# Servos.net
KiCad netlist of a schematic drawn in Altium Designer
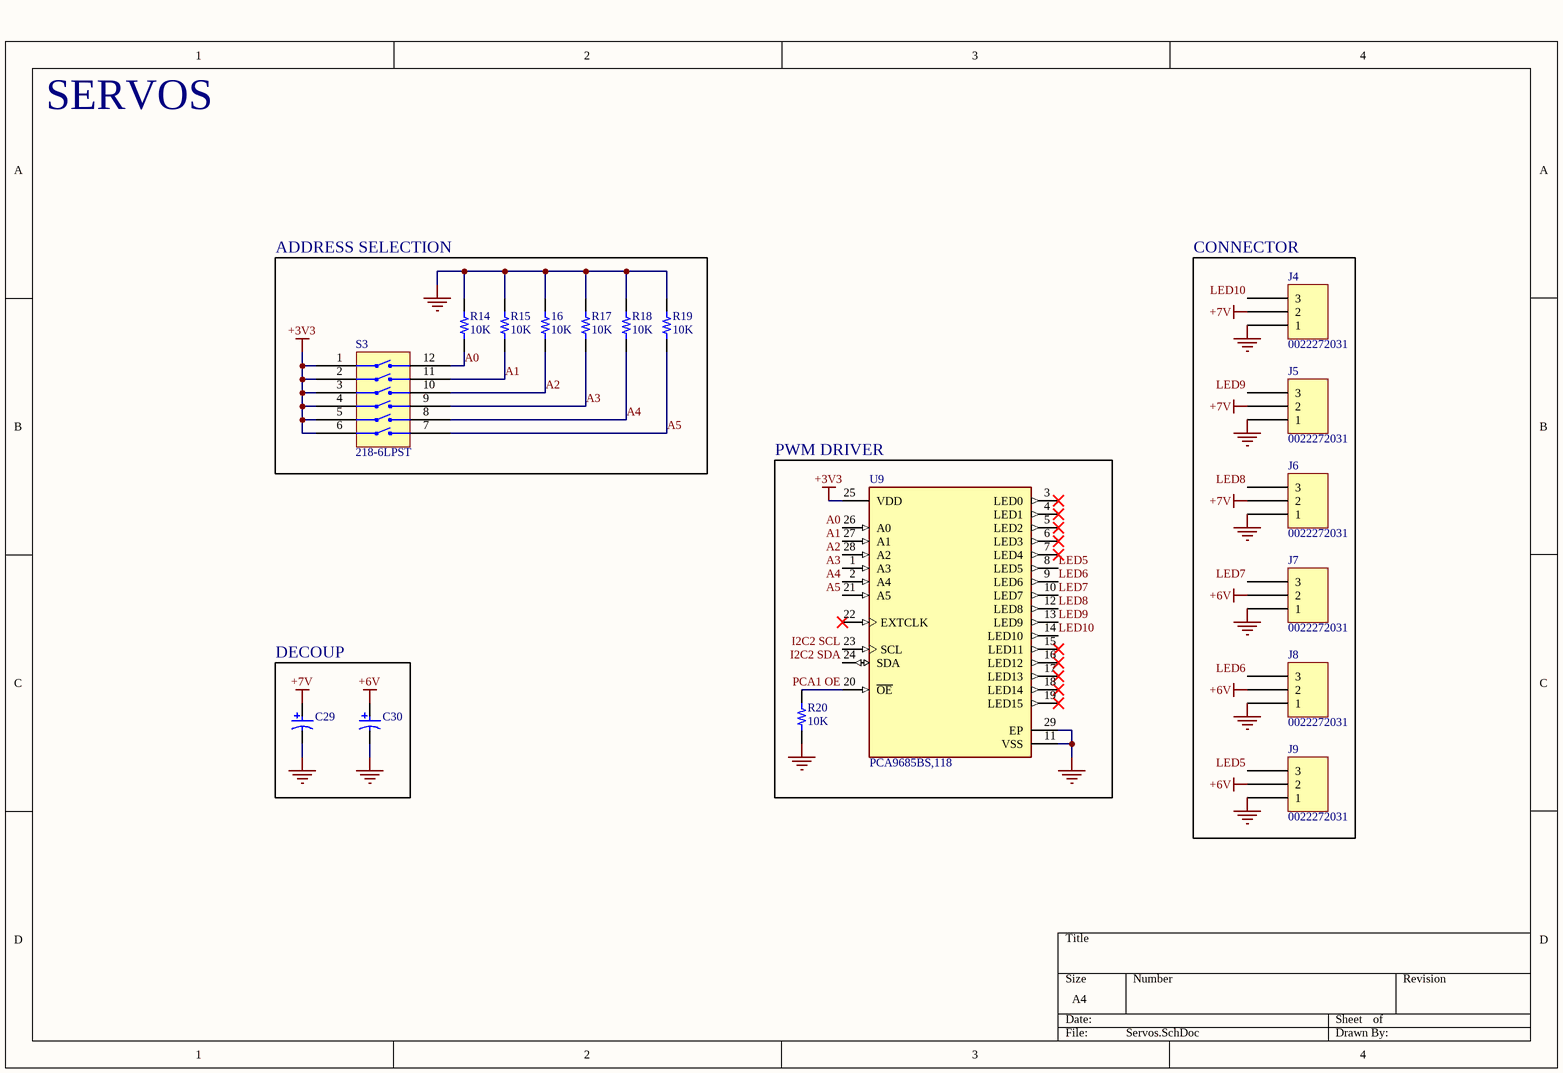
[diagram p0: Servos.SchDoc]

(export (version "E")
  (design (tool "Eeschema 10.0.6"))
  (components
    (comp (ref "16")
      (value "10K")
      (footprint "RES 0402_1005")
      (description "RES SMD 10K OHM 0.1% 1/16W 0402")
      (fields (field (name "PART NUMBER") "CPF0402B10KE"))
      (libsource (lib "Celestial Altium Library - altium_library") (part "Resistor"))
    )
    (comp (ref "C29")
      (value "~")
      (footprint "PNSC-FK-V-D8_V")
      (fields (field (name "MANUFACTURER") "Panasonic"))
      (libsource (lib "Altium Content Vault") (part "CAP-P-2"))
    )
    (comp (ref "C30")
      (value "~")
      (footprint "PNSC-FK-V-D8_V")
      (fields (field (name "MANUFACTURER") "Panasonic"))
      (libsource (lib "Altium Content Vault") (part "CAP-P-2"))
    )
    (comp (ref "J4")
      (value "0022272031")
      (footprint "MOLEX KK 0022272031")
      (description "CONN HEADER VERT 3POS 2.54MM")
      (libsource (lib "Celestial Altium Library - altium_library") (part "3 Pin"))
    )
    (comp (ref "J5")
      (value "0022272031")
      (footprint "MOLEX KK 0022272031")
      (description "CONN HEADER VERT 3POS 2.54MM")
      (libsource (lib "Celestial Altium Library - altium_library") (part "3 Pin"))
    )
    (comp (ref "J6")
      (value "0022272031")
      (footprint "MOLEX KK 0022272031")
      (description "CONN HEADER VERT 3POS 2.54MM")
      (libsource (lib "Celestial Altium Library - altium_library") (part "3 Pin"))
    )
    (comp (ref "J7")
      (value "0022272031")
      (footprint "MOLEX KK 0022272031")
      (description "CONN HEADER VERT 3POS 2.54MM")
      (libsource (lib "Celestial Altium Library - altium_library") (part "3 Pin"))
    )
    (comp (ref "J8")
      (value "0022272031")
      (footprint "MOLEX KK 0022272031")
      (description "CONN HEADER VERT 3POS 2.54MM")
      (libsource (lib "Celestial Altium Library - altium_library") (part "3 Pin"))
    )
    (comp (ref "J9")
      (value "0022272031")
      (footprint "MOLEX KK 0022272031")
      (description "CONN HEADER VERT 3POS 2.54MM")
      (libsource (lib "Celestial Altium Library - altium_library") (part "3 Pin"))
    )
    (comp (ref "R14")
      (value "10K")
      (footprint "RES 0402_1005")
      (description "RES SMD 10K OHM 0.1% 1/16W 0402")
      (fields (field (name "PART NUMBER") "CPF0402B10KE"))
      (libsource (lib "Celestial Altium Library - altium_library") (part "Resistor"))
    )
    (comp (ref "R15")
      (value "10K")
      (footprint "RES 0402_1005")
      (description "RES SMD 10K OHM 0.1% 1/16W 0402")
      (fields (field (name "PART NUMBER") "CPF0402B10KE"))
      (libsource (lib "Celestial Altium Library - altium_library") (part "Resistor"))
    )
    (comp (ref "R17")
      (value "10K")
      (footprint "RES 0402_1005")
      (description "RES SMD 10K OHM 0.1% 1/16W 0402")
      (fields (field (name "PART NUMBER") "CPF0402B10KE"))
      (libsource (lib "Celestial Altium Library - altium_library") (part "Resistor"))
    )
    (comp (ref "R18")
      (value "10K")
      (footprint "RES 0402_1005")
      (description "RES SMD 10K OHM 0.1% 1/16W 0402")
      (fields (field (name "PART NUMBER") "CPF0402B10KE"))
      (libsource (lib "Celestial Altium Library - altium_library") (part "Resistor"))
    )
    (comp (ref "R19")
      (value "10K")
      (footprint "RES 0402_1005")
      (description "RES SMD 10K OHM 0.1% 1/16W 0402")
      (fields (field (name "PART NUMBER") "CPF0402B10KE"))
      (libsource (lib "Celestial Altium Library - altium_library") (part "Resistor"))
    )
    (comp (ref "R20")
      (value "10K")
      (footprint "RES 0402_1005")
      (description "RES SMD 10K OHM 0.1% 1/16W 0402")
      (fields (field (name "PART NUMBER") "CPF0402B10KE"))
      (libsource (lib "Celestial Altium Library - altium_library") (part "Resistor"))
    )
    (comp (ref "S3")
      (value "218-6LPST")
      (footprint "CTS 218-6LPJ")
      (description "SWITCH SLIDE DIP SPST 25MA 24V")
      (libsource (lib "Celestial Altium Library - altium_library") (part "DIP SW 6P"))
    )
    (comp (ref "U9")
      (value "PCA9685BS,118")
      (footprint "FP-SOT788-1-IPC_B")
      (description "IC LED DRVR LIN DIM 25MA 28HVQFN")
      (libsource (lib "Altium Content Vault") (part "09cd7da67ee680d27754e98215877c2"))
    )
  )
  (nets
    (net (code "1") (name "+3V3") (class "Default")
      (node (ref "S3") (pin "1") (pinfunction "GND_1") (pintype "passive"))
      (node (ref "S3") (pin "2") (pinfunction "GND_2") (pintype "passive"))
      (node (ref "S3") (pin "3") (pinfunction "GND_3") (pintype "passive"))
      (node (ref "S3") (pin "4") (pinfunction "GND_4") (pintype "passive"))
      (node (ref "S3") (pin "5") (pinfunction "5_5") (pintype "passive"))
      (node (ref "S3") (pin "6") (pinfunction "6_6") (pintype "passive"))
      (node (ref "U9") (pin "25") (pinfunction "VDD_25") (pintype "power_in"))
    )
    (net (code "2") (name "+6V") (class "Default")
      (node (ref "C30") (pin "1") (pinfunction "1_1") (pintype "passive"))
      (node (ref "J7") (pin "2") (pinfunction "2_2") (pintype "passive"))
      (node (ref "J8") (pin "2") (pinfunction "2_2") (pintype "passive"))
      (node (ref "J9") (pin "2") (pinfunction "2_2") (pintype "passive"))
    )
    (net (code "3") (name "+7V") (class "Default")
      (node (ref "C29") (pin "1") (pinfunction "1_1") (pintype "passive"))
      (node (ref "J4") (pin "2") (pinfunction "2_2") (pintype "passive"))
      (node (ref "J5") (pin "2") (pinfunction "2_2") (pintype "passive"))
      (node (ref "J6") (pin "2") (pinfunction "2_2") (pintype "passive"))
    )
    (net (code "4") (name "/A0") (class "Default")
      (node (ref "R14") (pin "1") (pinfunction "1_1") (pintype "passive"))
      (node (ref "S3") (pin "12") (pinfunction "12_12") (pintype "passive"))
      (node (ref "U9") (pin "26") (pinfunction "A0_26") (pintype "input"))
    )
    (net (code "5") (name "/A1") (class "Default")
      (node (ref "R15") (pin "1") (pinfunction "1_1") (pintype "passive"))
      (node (ref "S3") (pin "11") (pinfunction "11_11") (pintype "passive"))
      (node (ref "U9") (pin "27") (pinfunction "A1_27") (pintype "input"))
    )
    (net (code "6") (name "/A2") (class "Default")
      (node (ref "16") (pin "1") (pinfunction "1_1") (pintype "passive"))
      (node (ref "S3") (pin "10") (pinfunction "10_10") (pintype "passive"))
      (node (ref "U9") (pin "28") (pinfunction "A2_28") (pintype "input"))
    )
    (net (code "7") (name "/A3") (class "Default")
      (node (ref "R17") (pin "1") (pinfunction "1_1") (pintype "passive"))
      (node (ref "S3") (pin "9") (pinfunction "9_9") (pintype "passive"))
      (node (ref "U9") (pin "1") (pinfunction "A3_1") (pintype "input"))
    )
    (net (code "8") (name "/A4") (class "Default")
      (node (ref "R18") (pin "1") (pinfunction "1_1") (pintype "passive"))
      (node (ref "S3") (pin "8") (pinfunction "8_8") (pintype "passive"))
      (node (ref "U9") (pin "2") (pinfunction "A4_2") (pintype "input"))
    )
    (net (code "9") (name "/A5") (class "Default")
      (node (ref "R19") (pin "1") (pinfunction "1_1") (pintype "passive"))
      (node (ref "S3") (pin "7") (pinfunction "7_7") (pintype "passive"))
      (node (ref "U9") (pin "21") (pinfunction "A5_21") (pintype "input"))
    )
    (net (code "10") (name "/I2C2 SCL") (class "Default")
      (node (ref "U9") (pin "23") (pinfunction "SCL_23") (pintype "input"))
    )
    (net (code "11") (name "/I2C2 SDA") (class "Default")
      (node (ref "U9") (pin "24") (pinfunction "SDA_24") (pintype "bidirectional"))
    )
    (net (code "12") (name "/LED5") (class "Default")
      (node (ref "J9") (pin "3") (pinfunction "3_3") (pintype "passive"))
      (node (ref "U9") (pin "8") (pinfunction "LED5_8") (pintype "output"))
    )
    (net (code "13") (name "/LED6") (class "Default")
      (node (ref "J8") (pin "3") (pinfunction "3_3") (pintype "passive"))
      (node (ref "U9") (pin "9") (pinfunction "LED6_9") (pintype "output"))
    )
    (net (code "14") (name "/LED7") (class "Default")
      (node (ref "J7") (pin "3") (pinfunction "3_3") (pintype "passive"))
      (node (ref "U9") (pin "10") (pinfunction "LED7_10") (pintype "output"))
    )
    (net (code "15") (name "/LED8") (class "Default")
      (node (ref "J6") (pin "3") (pinfunction "3_3") (pintype "passive"))
      (node (ref "U9") (pin "12") (pinfunction "LED8_12") (pintype "output"))
    )
    (net (code "16") (name "/LED9") (class "Default")
      (node (ref "J5") (pin "3") (pinfunction "3_3") (pintype "passive"))
      (node (ref "U9") (pin "13") (pinfunction "LED9_13") (pintype "output"))
    )
    (net (code "17") (name "/LED10") (class "Default")
      (node (ref "J4") (pin "3") (pinfunction "3_3") (pintype "passive"))
      (node (ref "U9") (pin "14") (pinfunction "LED10_14") (pintype "output"))
    )
    (net (code "18") (name "/PCA1 OE") (class "Default")
      (node (ref "R20") (pin "1") (pinfunction "1_1") (pintype "passive"))
      (node (ref "U9") (pin "20") (pinfunction "~{OE}_20") (pintype "input"))
    )
    (net (code "19") (name "GND") (class "Default")
      (node (ref "16") (pin "2") (pinfunction "2_2") (pintype "passive"))
      (node (ref "C29") (pin "2") (pinfunction "2_2") (pintype "passive"))
      (node (ref "C30") (pin "2") (pinfunction "2_2") (pintype "passive"))
      (node (ref "J4") (pin "1") (pinfunction "1_1") (pintype "passive"))
      (node (ref "J5") (pin "1") (pinfunction "1_1") (pintype "passive"))
      (node (ref "J6") (pin "1") (pinfunction "1_1") (pintype "passive"))
      (node (ref "J7") (pin "1") (pinfunction "1_1") (pintype "passive"))
      (node (ref "J8") (pin "1") (pinfunction "1_1") (pintype "passive"))
      (node (ref "J9") (pin "1") (pinfunction "1_1") (pintype "passive"))
      (node (ref "R14") (pin "2") (pinfunction "2_2") (pintype "passive"))
      (node (ref "R15") (pin "2") (pinfunction "2_2") (pintype "passive"))
      (node (ref "R17") (pin "2") (pinfunction "2_2") (pintype "passive"))
      (node (ref "R18") (pin "2") (pinfunction "2_2") (pintype "passive"))
      (node (ref "R19") (pin "2") (pinfunction "2_2") (pintype "passive"))
      (node (ref "R20") (pin "2") (pinfunction "2_2") (pintype "passive"))
      (node (ref "U9") (pin "11") (pinfunction "VSS_11") (pintype "power_in"))
      (node (ref "U9") (pin "29") (pinfunction "EP_29") (pintype "passive"))
    )
    (net (code "20") (name "unconnected-(U9-EXTCLK-Pad22)") (class "Default")
      (node (ref "U9") (pin "22") (pinfunction "EXTCLK_22") (pintype "input+no_connect"))
    )
    (net (code "21") (name "unconnected-(U9-LED0-Pad3)") (class "Default")
      (node (ref "U9") (pin "3") (pinfunction "LED0_3") (pintype "output+no_connect"))
    )
    (net (code "22") (name "unconnected-(U9-LED1-Pad4)") (class "Default")
      (node (ref "U9") (pin "4") (pinfunction "LED1_4") (pintype "output+no_connect"))
    )
    (net (code "23") (name "unconnected-(U9-LED2-Pad5)") (class "Default")
      (node (ref "U9") (pin "5") (pinfunction "LED2_5") (pintype "output+no_connect"))
    )
    (net (code "24") (name "unconnected-(U9-LED3-Pad6)") (class "Default")
      (node (ref "U9") (pin "6") (pinfunction "LED3_6") (pintype "output+no_connect"))
    )
    (net (code "25") (name "unconnected-(U9-LED4-Pad7)") (class "Default")
      (node (ref "U9") (pin "7") (pinfunction "LED4_7") (pintype "output+no_connect"))
    )
    (net (code "26") (name "unconnected-(U9-LED11-Pad15)") (class "Default")
      (node (ref "U9") (pin "15") (pinfunction "LED11_15") (pintype "output+no_connect"))
    )
    (net (code "27") (name "unconnected-(U9-LED12-Pad16)") (class "Default")
      (node (ref "U9") (pin "16") (pinfunction "LED12_16") (pintype "output+no_connect"))
    )
    (net (code "28") (name "unconnected-(U9-LED13-Pad17)") (class "Default")
      (node (ref "U9") (pin "17") (pinfunction "LED13_17") (pintype "output+no_connect"))
    )
    (net (code "29") (name "unconnected-(U9-LED14-Pad18)") (class "Default")
      (node (ref "U9") (pin "18") (pinfunction "LED14_18") (pintype "output+no_connect"))
    )
    (net (code "30") (name "unconnected-(U9-LED15-Pad19)") (class "Default")
      (node (ref "U9") (pin "19") (pinfunction "LED15_19") (pintype "output+no_connect"))
    )
  )
)
